# SensorBoard.net
KiCad netlist of a schematic drawn in Altium Designer
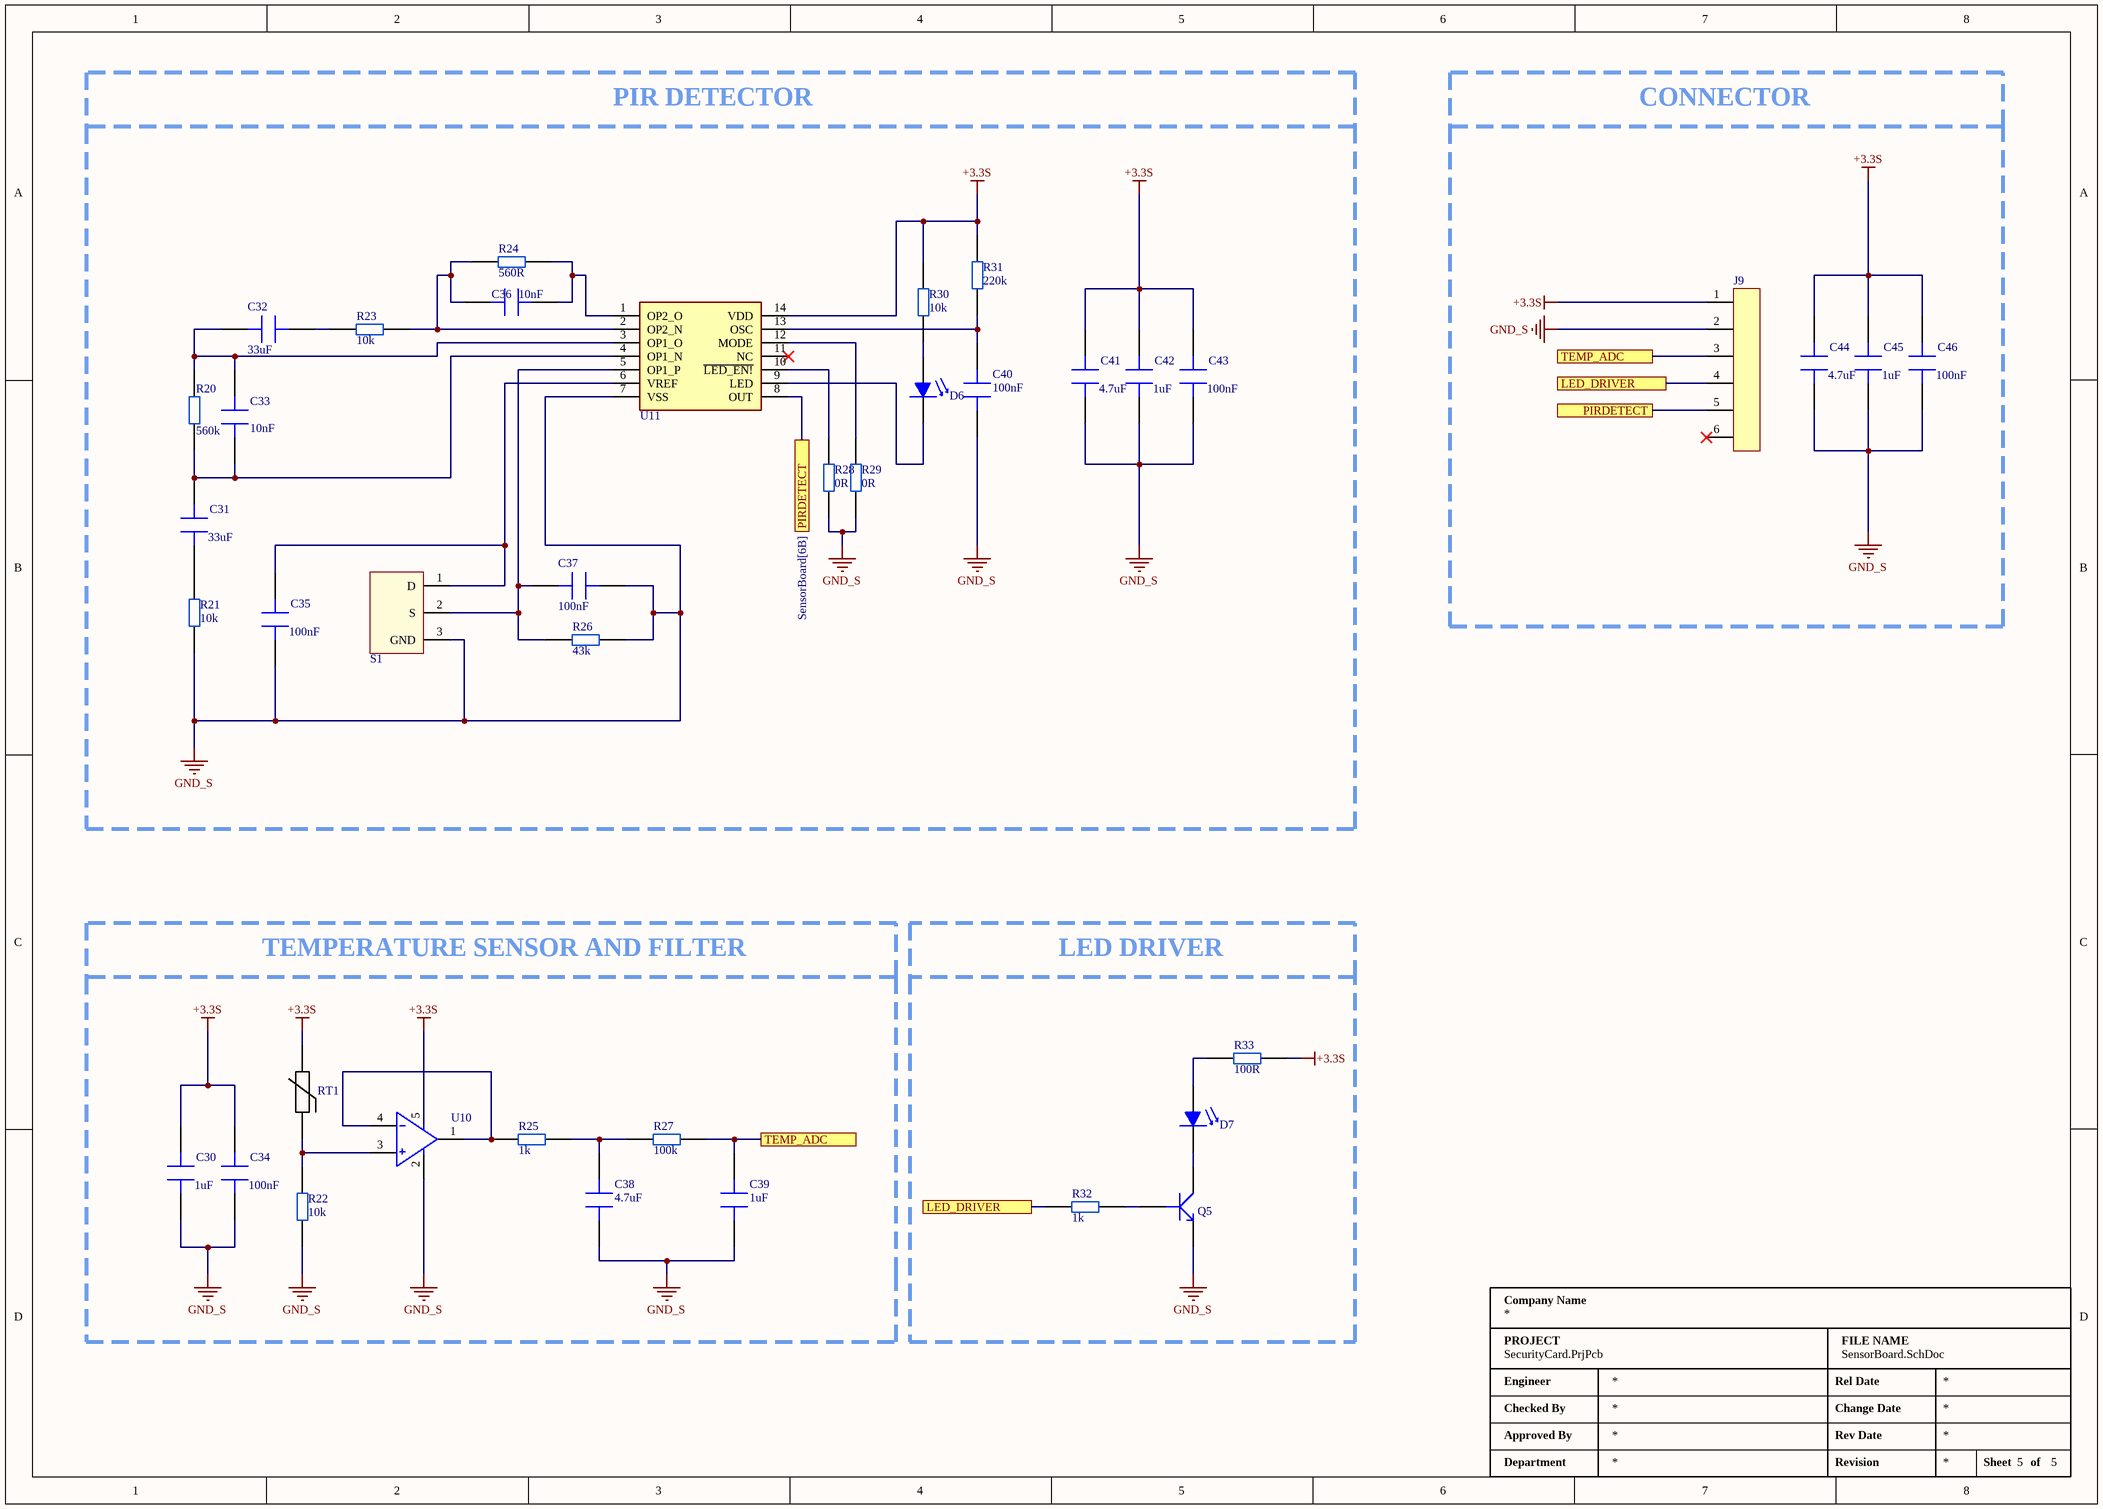
[diagram p0: SensorBoard.SchDoc]

(export (version "E")
  (design (tool "Eeschema 10.0.6"))
  (components
    (comp (ref "C30")
      (value "1uF")
      (footprint "CAP 0805")
      (description "Multilayer Ceramic Capacitor, 1 uF, 25 V, ï¿½ 10%, X7R, 0805 [2012 Metric]")
      (fields
        (field (name "MANUFACTURER") "KEMET")
        (field (name "MANUFACTURER PART NUMBER") "C0805C105K3RACTU")
      )
      (libsource (lib "SecurityLibray") (part "CAP MLCC 1uF 0805 MLCC"))
    )
    (comp (ref "C31")
      (value "33uF")
      (footprint "CAP 1206")
      (description "Multilayer Ceramic Capacitor, 33 uF, 25 V, ± 20%, X5R, 1206 [3216 Metric]")
      (fields
        (field (name "MANUFACTURER") "TDK")
        (field (name "MANUFACTURER PART NUMBER") "C3216X5R1E336M160AC")
        (field (name "DESIGNED BY") "SEFA")
      )
      (libsource (lib "SecurityLibray") (part "CAP MLCC 33uF 1206"))
    )
    (comp (ref "C32")
      (value "33uF")
      (footprint "CAP 1206")
      (description "Multilayer Ceramic Capacitor, 33 uF, 25 V, ± 20%, X5R, 1206 [3216 Metric]")
      (fields
        (field (name "MANUFACTURER") "TDK")
        (field (name "MANUFACTURER PART NUMBER") "C3216X5R1E336M160AC")
        (field (name "DESIGNED BY") "SEFA")
      )
      (libsource (lib "SecurityLibray") (part "CAP MLCC 33uF 1206"))
    )
    (comp (ref "C33")
      (value "10nF")
      (footprint "CAP 0603")
      (description "Multilayer Ceramic Capacitor, 0.01 uF, 50 V, ± 10%, X7R, 0603 [1608 Metric]")
      (fields
        (field (name "MANUFACTURER") "Yageo")
        (field (name "MANUFACTURER PART NUMBER") "CC0603KRX7R9BB103")
        (field (name "DESIGNED BY") "SEFA")
      )
      (libsource (lib "SecurityLibray") (part "CAP MLCC 10nF 0603"))
    )
    (comp (ref "C34")
      (value "100nF")
      (footprint "CAP 0805")
      (description "Multilayer Ceramic Capacitor, 0.1 uF, 50 V, ± 10%, X7R, 0805 [2012 Metric]")
      (fields
        (field (name "MANUFACTURER") "Yageo")
        (field (name "MANUFACTURER PART NUMBER") "CC0805KRX7R9BB104")
      )
      (libsource (lib "SecurityLibray") (part "CAP MLCC 100nF 0805"))
    )
    (comp (ref "C35")
      (value "100nF")
      (footprint "CAP 0603")
      (description "Multilayer Ceramic Capacitor, 0.1 uF, 50 V, ± 10%, X7R, 0603 [1608 Metric]")
      (fields
        (field (name "MANUFACTURER") "Kyocera AVX")
        (field (name "MANUFACTURER PART NUMBER") "06035C104K4T2A")
        (field (name "DESIGNED BY") "SEFA")
      )
      (libsource (lib "SecurityLibray") (part "CAP MLCC 100nF 0603"))
    )
    (comp (ref "C36")
      (value "10nF")
      (footprint "CAP 0603")
      (description "Multilayer Ceramic Capacitor, 0.01 uF, 50 V, ± 10%, X7R, 0603 [1608 Metric]")
      (fields
        (field (name "MANUFACTURER") "Yageo")
        (field (name "MANUFACTURER PART NUMBER") "CC0603KRX7R9BB103")
        (field (name "DESIGNED BY") "SEFA")
      )
      (libsource (lib "SecurityLibray") (part "CAP MLCC 10nF 0603"))
    )
    (comp (ref "C37")
      (value "100nF")
      (footprint "CAP 0603")
      (description "Multilayer Ceramic Capacitor, 0.1 uF, 50 V, ± 10%, X7R, 0603 [1608 Metric]")
      (fields
        (field (name "MANUFACTURER") "Kyocera AVX")
        (field (name "MANUFACTURER PART NUMBER") "06035C104K4T2A")
        (field (name "DESIGNED BY") "SEFA")
      )
      (libsource (lib "SecurityLibray") (part "CAP MLCC 100nF 0603"))
    )
    (comp (ref "C38")
      (value "4.7uF")
      (footprint "CAP 0805")
      (description "Multilayer Ceramic Capacitor, 4.7 uF, 25 V, ± 10%, X5R, 0805 [2012 Metric]")
      (fields
        (field (name "MANUFACTURER") "Samsung")
        (field (name "MANUFACTURER PART NUMBER") "CL21A475KAQNNNE")
        (field (name "DESIGNED BY") "SEFA")
      )
      (libsource (lib "SecurityLibray") (part "CAP MLCC 4.7uF 0805 MLCC"))
    )
    (comp (ref "C39")
      (value "1uF")
      (footprint "CAP 0805")
      (description "Multilayer Ceramic Capacitor, 1 uF, 25 V, ï¿½ 10%, X7R, 0805 [2012 Metric]")
      (fields
        (field (name "MANUFACTURER") "KEMET")
        (field (name "MANUFACTURER PART NUMBER") "C0805C105K3RACTU")
      )
      (libsource (lib "SecurityLibray") (part "CAP MLCC 1uF 0805 MLCC"))
    )
    (comp (ref "C40")
      (value "100nF")
      (footprint "CAP 0603")
      (description "Multilayer Ceramic Capacitor, 0.1 uF, 50 V, ± 10%, X7R, 0603 [1608 Metric]")
      (fields
        (field (name "MANUFACTURER") "Kyocera AVX")
        (field (name "MANUFACTURER PART NUMBER") "06035C104K4T2A")
        (field (name "DESIGNED BY") "SEFA")
      )
      (libsource (lib "SecurityLibray") (part "CAP MLCC 100nF 0603"))
    )
    (comp (ref "C41")
      (value "4.7uF")
      (footprint "CAP 0805")
      (description "Multilayer Ceramic Capacitor, 4.7 uF, 25 V, ± 10%, X5R, 0805 [2012 Metric]")
      (fields
        (field (name "MANUFACTURER") "Samsung")
        (field (name "MANUFACTURER PART NUMBER") "CL21A475KAQNNNE")
        (field (name "DESIGNED BY") "SEFA")
      )
      (libsource (lib "SecurityLibray") (part "CAP MLCC 4.7uF 0805 MLCC"))
    )
    (comp (ref "C42")
      (value "1uF")
      (footprint "CAP 0805")
      (description "Multilayer Ceramic Capacitor, 1 uF, 25 V, ï¿½ 10%, X7R, 0805 [2012 Metric]")
      (fields
        (field (name "MANUFACTURER") "KEMET")
        (field (name "MANUFACTURER PART NUMBER") "C0805C105K3RACTU")
      )
      (libsource (lib "SecurityLibray") (part "CAP MLCC 1uF 0805 MLCC"))
    )
    (comp (ref "C43")
      (value "100nF")
      (footprint "CAP 0805")
      (description "Multilayer Ceramic Capacitor, 0.1 uF, 50 V, ± 10%, X7R, 0805 [2012 Metric]")
      (fields
        (field (name "MANUFACTURER") "Yageo")
        (field (name "MANUFACTURER PART NUMBER") "CC0805KRX7R9BB104")
      )
      (libsource (lib "SecurityLibray") (part "CAP MLCC 100nF 0805"))
    )
    (comp (ref "C44")
      (value "4.7uF")
      (footprint "CAP 0805")
      (description "Multilayer Ceramic Capacitor, 4.7 uF, 25 V, ± 10%, X5R, 0805 [2012 Metric]")
      (fields
        (field (name "MANUFACTURER") "Samsung")
        (field (name "MANUFACTURER PART NUMBER") "CL21A475KAQNNNE")
        (field (name "DESIGNED BY") "SEFA")
      )
      (libsource (lib "SecurityLibray") (part "CAP MLCC 4.7uF 0805 MLCC"))
    )
    (comp (ref "C45")
      (value "1uF")
      (footprint "CAP 0805")
      (description "Multilayer Ceramic Capacitor, 1 uF, 25 V, ï¿½ 10%, X7R, 0805 [2012 Metric]")
      (fields
        (field (name "MANUFACTURER") "KEMET")
        (field (name "MANUFACTURER PART NUMBER") "C0805C105K3RACTU")
      )
      (libsource (lib "SecurityLibray") (part "CAP MLCC 1uF 0805 MLCC"))
    )
    (comp (ref "C46")
      (value "100nF")
      (footprint "CAP 0805")
      (description "Multilayer Ceramic Capacitor, 0.1 uF, 50 V, ± 10%, X7R, 0805 [2012 Metric]")
      (fields
        (field (name "MANUFACTURER") "Yageo")
        (field (name "MANUFACTURER PART NUMBER") "CC0805KRX7R9BB104")
      )
      (libsource (lib "SecurityLibray") (part "CAP MLCC 100nF 0805"))
    )
    (comp (ref "D6")
      (value "LED GREEN CLEAR 0805 SMD")
      (footprint "LED 0805")
      (description "WURTH ELEKTRONIK - 150080GS75000 - LED, Green, SMD, 0805, 30 mA, 3.2 V, 520 nm")
      (fields
        (field (name "MANUFACTURER") "Wurth Electronics")
        (field (name "MANUFACTURER PART NUMBER") "150080GS75000")
        (field (name "DESIGNED BY") "SEFA")
      )
      (libsource (lib "SecurityLibray") (part "LED GREEN 0805"))
    )
    (comp (ref "D7")
      (value "LED RED CLEAR 0805 SMD")
      (footprint "LED 0805")
      (description "LED Uni-Color Red 630nm 2-Pin Chip 0805(2012Metric) T/R")
      (fields
        (field (name "MANUFACTURER") "Wurth Electronics")
        (field (name "MANUFACTURER PART NUMBER") "150080RS75000")
        (field (name "DESIGNED BY") "SEFA")
      )
      (libsource (lib "SecurityLibray") (part "LED RED 0805"))
    )
    (comp (ref "J9")
      (value "CONN HEADER VERT 6POS 1.5MM")
      (footprint "TUNIK 6P 2.5mm")
      (description "Header B6B-ZR, 1.50mm, 6-contacts, top entry, THT, /2000/box")
      (fields
        (field (name "MANUFACTURER") "JST")
        (field (name "MANUFACTURER PART NUMBER") "B6B-ZR")
        (field (name "DESIGNED BY") "SEFA")
      )
      (libsource (lib "SecurityLibray") (part "TUNIK 6P 2.5mm"))
    )
    (comp (ref "Q5")
      (value "TRANS NPN 40V 0.2A SOT23")
      (footprint "SOT-23-3")
      (description "Transistor: NPN; bipolar; 40V; 0.2A; 350mW; -55+150 deg.C; SMD; SOT23")
      (fields
        (field (name "MANUFACTURER") "Diotec")
        (field (name "MANUFACTURER PART NUMBER") "MMBT3904")
        (field (name "DESIGNED BY") "SEFA")
      )
      (libsource (lib "SecurityLibray") (part "MMBT3904 NPN TR"))
    )
    (comp (ref "R20")
      (value "560k")
      (footprint "RES 0603")
      (description "SMD Chip Resistor, 560 kOhm, ± 5%, 100 mW, 0603 [1608 Metric], Thick Film, General Purpose")
      (fields
        (field (name "MANUFACTURER") "Yageo")
        (field (name "MANUFACTURER PART NUMBER") "RC0603JR-07560KL")
        (field (name "DESIGNED BY") "SEFA")
      )
      (libsource (lib "SecurityLibray") (part "RES 560k OHM 0603"))
    )
    (comp (ref "R21")
      (value "10k")
      (footprint "RES 0603")
      (description "Res Thick Film 0603 10K Ohm 5% 1/10W ±100ppm/°C Molded SMD SMD Paper T/R")
      (fields
        (field (name "MANUFACTURER") "Stackpole Electronics")
        (field (name "MANUFACTURER PART NUMBER") "RMCF0603JT10K0")
        (field (name "DESIGNED BY") "SEFA")
      )
      (libsource (lib "SecurityLibray") (part "RES 10K OHM 0603"))
    )
    (comp (ref "R22")
      (value "10k")
      (footprint "RES 0603")
      (description "Res Thick Film 0603 10K Ohm 5% 1/10W ±100ppm/°C Molded SMD SMD Paper T/R")
      (fields
        (field (name "MANUFACTURER") "Stackpole Electronics")
        (field (name "MANUFACTURER PART NUMBER") "RMCF0603JT10K0")
        (field (name "DESIGNED BY") "SEFA")
      )
      (libsource (lib "SecurityLibray") (part "RES 10K OHM 0603"))
    )
    (comp (ref "R23")
      (value "10k")
      (footprint "RES 0603")
      (description "Res Thick Film 0603 10K Ohm 5% 1/10W ±100ppm/°C Molded SMD SMD Paper T/R")
      (fields
        (field (name "MANUFACTURER") "Stackpole Electronics")
        (field (name "MANUFACTURER PART NUMBER") "RMCF0603JT10K0")
        (field (name "DESIGNED BY") "SEFA")
      )
      (libsource (lib "") (part "RES 10K OHM 0603_1"))
    )
    (comp (ref "R24")
      (value "560R")
      (footprint "RES 0603")
      (description "SMD Chip Resistor, 560 Ohm, ± 1%, 100 mW, 0603 [1608 Metric], Thick Film, General Purpose")
      (fields
        (field (name "MANUFACTURER") "Yageo")
        (field (name "MANUFACTURER PART NUMBER") "RC0603FR-07560RL")
        (field (name "DESIGNED BY") "SEFA")
      )
      (libsource (lib "SecurityLibray") (part "RES 560R OHM 0603"))
    )
    (comp (ref "R25")
      (value "1k")
      (footprint "RES 0603")
      (description "Res Thick Film 0603 10K Ohm 5% 1/10W ±100ppm/°C Molded SMD SMD Paper T/R")
      (fields
        (field (name "MANUFACTURER") "Stackpole Electronics")
        (field (name "MANUFACTURER PART NUMBER") "RMCF0603JT10K0")
        (field (name "DESIGNED BY") "SEFA")
      )
      (libsource (lib "") (part "RES 10K OHM 0603_2"))
    )
    (comp (ref "R26")
      (value "43k")
      (footprint "RES 0603")
      (description "SMD Chip Resistor, 43 kOhm, ± 1%, 100 mW, 0603 [1608 Metric], Thick Film, General Purpose")
      (fields
        (field (name "MANUFACTURER") "Yageo")
        (field (name "MANUFACTURER PART NUMBER") "RC0603FR-0743KL")
        (field (name "DESIGNED BY") "SEFA")
      )
      (libsource (lib "SecurityLibray") (part "RES 43k OHM 0603"))
    )
    (comp (ref "R27")
      (value "100k")
      (footprint "RES 0603")
      (description "Res Thick Film 0603 10K Ohm 5% 1/10W ±100ppm/°C Molded SMD SMD Paper T/R")
      (fields
        (field (name "MANUFACTURER") "Stackpole Electronics")
        (field (name "MANUFACTURER PART NUMBER") "RMCF0603JT10K0")
        (field (name "DESIGNED BY") "SEFA")
      )
      (libsource (lib "") (part "RES 10K OHM 0603_2"))
    )
    (comp (ref "R28")
      (value "0R")
      (footprint "RES 0603")
      (description "GENERAL PURPOSE CHIP RESISTOR Metal Glaze/thick Film, 0.1W, 0ohm, Surface Mount, 0603")
      (fields
        (field (name "MANUFACTURER") "Yageo")
        (field (name "MANUFACTURER PART NUMBER") "RC0603JR-070RL")
        (field (name "DESIGNED BY") "SEFA")
      )
      (libsource (lib "SecurityLibray") (part "RES 0R OHM 0603"))
    )
    (comp (ref "R29")
      (value "0R")
      (footprint "RES 0603")
      (description "GENERAL PURPOSE CHIP RESISTOR Metal Glaze/thick Film, 0.1W, 0ohm, Surface Mount, 0603")
      (fields
        (field (name "MANUFACTURER") "Yageo")
        (field (name "MANUFACTURER PART NUMBER") "RC0603JR-070RL")
        (field (name "DESIGNED BY") "SEFA")
      )
      (libsource (lib "SecurityLibray") (part "RES 0R OHM 0603"))
    )
    (comp (ref "R30")
      (value "10k")
      (footprint "RES 0603")
      (description "Res Thick Film 0603 10K Ohm 5% 1/10W ±100ppm/°C Molded SMD SMD Paper T/R")
      (fields
        (field (name "MANUFACTURER") "Stackpole Electronics")
        (field (name "MANUFACTURER PART NUMBER") "RMCF0603JT10K0")
        (field (name "DESIGNED BY") "SEFA")
      )
      (libsource (lib "SecurityLibray") (part "RES 10K OHM 0603"))
    )
    (comp (ref "R31")
      (value "220k")
      (footprint "RES 0603")
      (description "Res Thick Film 0603 220K Ohm 1% 0.1W(1/10W) ±100ppm/C Pad SMD Automotive T/R")
      (fields
        (field (name "MANUFACTURER") "Stackpole Electronics")
        (field (name "MANUFACTURER PART NUMBER") "RMCF0603FT220K")
        (field (name "DESIGNED BY") "SEFA")
      )
      (libsource (lib "SecurityLibray") (part "RES 220k OHM 0603"))
    )
    (comp (ref "R32")
      (value "1k")
      (footprint "RES 0603")
      (description "Res Thick Film 0603 10K Ohm 5% 1/10W ±100ppm/°C Molded SMD SMD Paper T/R")
      (fields
        (field (name "MANUFACTURER") "Stackpole Electronics")
        (field (name "MANUFACTURER PART NUMBER") "RMCF0603JT10K0")
        (field (name "DESIGNED BY") "SEFA")
      )
      (libsource (lib "") (part "RES 10K OHM 0603_1"))
    )
    (comp (ref "R33")
      (value "100R")
      (footprint "RES 0603")
      (description "Res Thick Film 0603 10K Ohm 5% 1/10W ±100ppm/°C Molded SMD SMD Paper T/R")
      (fields
        (field (name "MANUFACTURER") "Stackpole Electronics")
        (field (name "MANUFACTURER PART NUMBER") "RMCF0603JT10K0")
        (field (name "DESIGNED BY") "SEFA")
      )
      (libsource (lib "") (part "RES 10K OHM 0603_1"))
    )
    (comp (ref "RT1")
      (value "SENSOR PTC 10KOHM 1% 1206")
      (footprint "RES1206")
      (description "Thermistor PTC 10K Ohm 1% 2-Pin 1206 Surface Mount Solder Pad T/R Automotive")
      (fields
        (field (name "MANUFACTURER") "Vishay Dale")
        (field (name "MANUFACTURER PART NUMBER") "TFPT1206L1002FM")
      )
      (libsource (lib "SecurityLibray") (part "TFPT1206L1002FM"))
    )
    (comp (ref "S1")
      (value "LHI 878/3902")
      (footprint "LHI 878")
      (description "SENSOR PYRO DETECTOR DUAL MOTION")
      (fields
        (field (name "MANUFACTURER") "Excelitas")
        (field (name "MANUFACTURER PART NUMBER") "LHI878")
        (field (name "DESIGNED") "SEFA")
      )
      (libsource (lib "SecurityLibray") (part "LHI 878/3902"))
    )
    (comp (ref "U10")
      (value "IC OPAMP GP 1 CIRCUIT SOT23-5")
      (footprint "SOT-23-5")
      (description "IC OPAMP GP 3MHZ RRO SOT23-5")
      (fields
        (field (name "MANUFACTURER") "Texas Instruments")
        (field (name "MANUFACTURER PART NUMBER") "OPA314AIDBVR")
        (field (name "DESIGNED BY") "SEFA")
      )
      (libsource (lib "SecurityLibray") (part "OPA314AIDBVR GPA"))
    )
    (comp (ref "U11")
      (value "IC PIR DETECTOR CTLR 14SOIC")
      (footprint "SOIC14")
      (description "NCS36000 Series Single 5.75V Passive Infrared Detector Controller (PIR) -SOIC-14")
      (fields
        (field (name "MANUFACTURER") "ON Semiconductor")
        (field (name "MANUFACTURER PART NUMBER") "NCS36000DRG")
        (field (name "DESIGNED BY") "SEFA")
      )
      (libsource (lib "SecurityLibray") (part "NCS36000DRG"))
    )
  )
  (nets
    (net (code "1") (name "+3.3S") (class "Default")
      (node (ref "C30") (pin "2") (pinfunction "2_2") (pintype "passive"))
      (node (ref "C34") (pin "2") (pinfunction "2_2") (pintype "passive"))
      (node (ref "C41") (pin "2") (pinfunction "2_2") (pintype "passive"))
      (node (ref "C42") (pin "2") (pinfunction "2_2") (pintype "passive"))
      (node (ref "C43") (pin "2") (pinfunction "2_2") (pintype "passive"))
      (node (ref "C44") (pin "2") (pinfunction "2_2") (pintype "passive"))
      (node (ref "C45") (pin "2") (pinfunction "2_2") (pintype "passive"))
      (node (ref "C46") (pin "2") (pinfunction "2_2") (pintype "passive"))
      (node (ref "J9") (pin "1") (pintype "passive"))
      (node (ref "R30") (pin "2") (pinfunction "2_2") (pintype "passive"))
      (node (ref "R31") (pin "2") (pinfunction "2_2") (pintype "passive"))
      (node (ref "R33") (pin "2") (pinfunction "2_2") (pintype "passive"))
      (node (ref "RT1") (pin "2") (pinfunction "2_2") (pintype "passive"))
      (node (ref "U10") (pin "5") (pinfunction "V+_5") (pintype "passive"))
      (node (ref "U11") (pin "14") (pinfunction "VDD_14") (pintype "passive"))
    )
    (net (code "2") (name "/LED_DRIVER") (class "Default")
      (node (ref "J9") (pin "4") (pintype "passive"))
      (node (ref "R32") (pin "1") (pinfunction "1_1") (pintype "passive"))
    )
    (net (code "3") (name "/PIRDETECT") (class "Default")
      (node (ref "J9") (pin "5") (pintype "passive"))
      (node (ref "U11") (pin "8") (pinfunction "OUT_8") (pintype "passive"))
    )
    (net (code "4") (name "/TEMP_ADC") (class "Default")
      (node (ref "C39") (pin "2") (pinfunction "2_2") (pintype "passive"))
      (node (ref "J9") (pin "3") (pintype "passive"))
      (node (ref "R27") (pin "1") (pinfunction "1_1") (pintype "passive"))
    )
    (net (code "5") (name "GND_S") (class "Default")
      (node (ref "C30") (pin "1") (pinfunction "1_1") (pintype "passive"))
      (node (ref "C34") (pin "1") (pinfunction "1_1") (pintype "passive"))
      (node (ref "C35") (pin "1") (pinfunction "1_1") (pintype "passive"))
      (node (ref "C37") (pin "1") (pinfunction "1_1") (pintype "passive"))
      (node (ref "C38") (pin "1") (pinfunction "1_1") (pintype "passive"))
      (node (ref "C39") (pin "1") (pinfunction "1_1") (pintype "passive"))
      (node (ref "C40") (pin "2") (pinfunction "2_2") (pintype "passive"))
      (node (ref "C41") (pin "1") (pinfunction "1_1") (pintype "passive"))
      (node (ref "C42") (pin "1") (pinfunction "1_1") (pintype "passive"))
      (node (ref "C43") (pin "1") (pinfunction "1_1") (pintype "passive"))
      (node (ref "C44") (pin "1") (pinfunction "1_1") (pintype "passive"))
      (node (ref "C45") (pin "1") (pinfunction "1_1") (pintype "passive"))
      (node (ref "C46") (pin "1") (pinfunction "1_1") (pintype "passive"))
      (node (ref "J9") (pin "2") (pintype "passive"))
      (node (ref "Q5") (pin "2") (pinfunction "E_2") (pintype "passive"))
      (node (ref "R21") (pin "1") (pinfunction "1_1") (pintype "passive"))
      (node (ref "R22") (pin "1") (pinfunction "1_1") (pintype "passive"))
      (node (ref "R26") (pin "1") (pinfunction "1_1") (pintype "passive"))
      (node (ref "R28") (pin "1") (pinfunction "1_1") (pintype "passive"))
      (node (ref "R29") (pin "1") (pinfunction "1_1") (pintype "passive"))
      (node (ref "S1") (pin "3") (pinfunction "GND_3") (pintype "passive"))
      (node (ref "U11") (pin "7") (pinfunction "VSS_7") (pintype "passive"))
    )
    (net (code "6") (name "Net-(C31-Pad1)") (class "Default")
      (node (ref "C31") (pin "1") (pinfunction "1_1") (pintype "passive"))
      (node (ref "R21") (pin "2") (pinfunction "2_2") (pintype "passive"))
    )
    (net (code "7") (name "Net-(C32-Pad2)") (class "Default")
      (node (ref "C32") (pin "2") (pinfunction "2_2") (pintype "passive"))
      (node (ref "R23") (pin "1") (pinfunction "1_1") (pintype "passive"))
    )
    (net (code "8") (name "Net-(C38-Pad2)") (class "Default")
      (node (ref "C38") (pin "2") (pinfunction "2_2") (pintype "passive"))
      (node (ref "R25") (pin "1") (pinfunction "1_1") (pintype "passive"))
      (node (ref "R27") (pin "2") (pinfunction "2_2") (pintype "passive"))
    )
    (net (code "9") (name "Net-(D6-1)") (class "Default")
      (node (ref "D6") (pin "A") (pinfunction "1_A") (pintype "passive"))
      (node (ref "R30") (pin "1") (pinfunction "1_1") (pintype "passive"))
    )
    (net (code "10") (name "Net-(D6-2)") (class "Default")
      (node (ref "D6") (pin "C") (pinfunction "2_C") (pintype "passive"))
      (node (ref "U11") (pin "9") (pinfunction "LED_9") (pintype "passive"))
    )
    (net (code "11") (name "Net-(D7-1)") (class "Default")
      (node (ref "D7") (pin "A") (pinfunction "1_A") (pintype "passive"))
      (node (ref "R33") (pin "1") (pinfunction "1_1") (pintype "passive"))
    )
    (net (code "12") (name "Net-(D7-2)") (class "Default")
      (node (ref "D7") (pin "C") (pinfunction "2_C") (pintype "passive"))
      (node (ref "Q5") (pin "3") (pinfunction "C_3") (pintype "passive"))
    )
    (net (code "13") (name "Net-(Q5-B)") (class "Default")
      (node (ref "Q5") (pin "1") (pinfunction "B_1") (pintype "passive"))
      (node (ref "R32") (pin "2") (pinfunction "2_2") (pintype "passive"))
    )
    (net (code "14") (name "Net-(S1-D)") (class "Default")
      (node (ref "C35") (pin "2") (pinfunction "2_2") (pintype "passive"))
      (node (ref "S1") (pin "1") (pinfunction "D_1") (pintype "passive"))
      (node (ref "U11") (pin "6") (pinfunction "VREF_6") (pintype "passive"))
    )
    (net (code "15") (name "Net-(S1-S)") (class "Default")
      (node (ref "C37") (pin "2") (pinfunction "2_2") (pintype "passive"))
      (node (ref "R26") (pin "2") (pinfunction "2_2") (pintype "passive"))
      (node (ref "S1") (pin "2") (pinfunction "S_2") (pintype "passive"))
      (node (ref "U11") (pin "5") (pinfunction "OP1_P_5") (pintype "passive"))
    )
    (net (code "16") (name "Net-(U10-+IN)") (class "Default")
      (node (ref "R22") (pin "2") (pinfunction "2_2") (pintype "passive"))
      (node (ref "RT1") (pin "1") (pinfunction "1_1") (pintype "passive"))
      (node (ref "U10") (pin "3") (pinfunction "+IN_3") (pintype "passive"))
    )
    (net (code "17") (name "Net-(U10--IN)") (class "Default")
      (node (ref "R25") (pin "2") (pinfunction "2_2") (pintype "passive"))
      (node (ref "U10") (pin "1") (pinfunction "OUT_1") (pintype "passive"))
      (node (ref "U10") (pin "4") (pinfunction "-IN_4") (pintype "passive"))
    )
    (net (code "18") (name "Net-(U11-MODE)") (class "Default")
      (node (ref "R29") (pin "2") (pinfunction "2_2") (pintype "passive"))
      (node (ref "U11") (pin "12") (pinfunction "MODE_12") (pintype "passive"))
    )
    (net (code "19") (name "Net-(U11-OP1_N)") (class "Default")
      (node (ref "C31") (pin "2") (pinfunction "2_2") (pintype "passive"))
      (node (ref "C33") (pin "1") (pinfunction "1_1") (pintype "passive"))
      (node (ref "R20") (pin "1") (pinfunction "1_1") (pintype "passive"))
      (node (ref "U11") (pin "4") (pinfunction "OP1_N_4") (pintype "passive"))
    )
    (net (code "20") (name "Net-(U11-OP1_O)") (class "Default")
      (node (ref "C32") (pin "1") (pinfunction "1_1") (pintype "passive"))
      (node (ref "C33") (pin "2") (pinfunction "2_2") (pintype "passive"))
      (node (ref "R20") (pin "2") (pinfunction "2_2") (pintype "passive"))
      (node (ref "U11") (pin "3") (pinfunction "OP1_O_3") (pintype "passive"))
    )
    (net (code "21") (name "Net-(U11-OP2_N)") (class "Default")
      (node (ref "C36") (pin "1") (pinfunction "1_1") (pintype "passive"))
      (node (ref "R23") (pin "2") (pinfunction "2_2") (pintype "passive"))
      (node (ref "R24") (pin "1") (pinfunction "1_1") (pintype "passive"))
      (node (ref "U11") (pin "2") (pinfunction "OP2_N_2") (pintype "passive"))
    )
    (net (code "22") (name "Net-(U11-OP2_O)") (class "Default")
      (node (ref "C36") (pin "2") (pinfunction "2_2") (pintype "passive"))
      (node (ref "R24") (pin "2") (pinfunction "2_2") (pintype "passive"))
      (node (ref "U11") (pin "1") (pinfunction "OP2_O_1") (pintype "passive"))
    )
    (net (code "23") (name "Net-(U11-OSC)") (class "Default")
      (node (ref "C40") (pin "1") (pinfunction "1_1") (pintype "passive"))
      (node (ref "R31") (pin "1") (pinfunction "1_1") (pintype "passive"))
      (node (ref "U11") (pin "13") (pinfunction "OSC_13") (pintype "passive"))
    )
    (net (code "24") (name "Net-(U11-~{LED_EN!})") (class "Default")
      (node (ref "R28") (pin "2") (pinfunction "2_2") (pintype "passive"))
      (node (ref "U11") (pin "10") (pinfunction "~{LED_EN!}_10") (pintype "passive"))
    )
    (net (code "25") (name "unconnected-(J9-Pad6)") (class "Default")
      (node (ref "J9") (pin "6") (pintype "passive+no_connect"))
    )
    (net (code "26") (name "unconnected-(U10-V--Pad2)") (class "Default")
      (node (ref "U10") (pin "2") (pinfunction "V-_2") (pintype "passive"))
    )
    (net (code "27") (name "unconnected-(U11-NC-Pad11)") (class "Default")
      (node (ref "U11") (pin "11") (pinfunction "NC_11") (pintype "passive+no_connect"))
    )
  )
)
